# 0_8mm_Layers.net
KiCad netlist of a schematic drawn in EAGLE
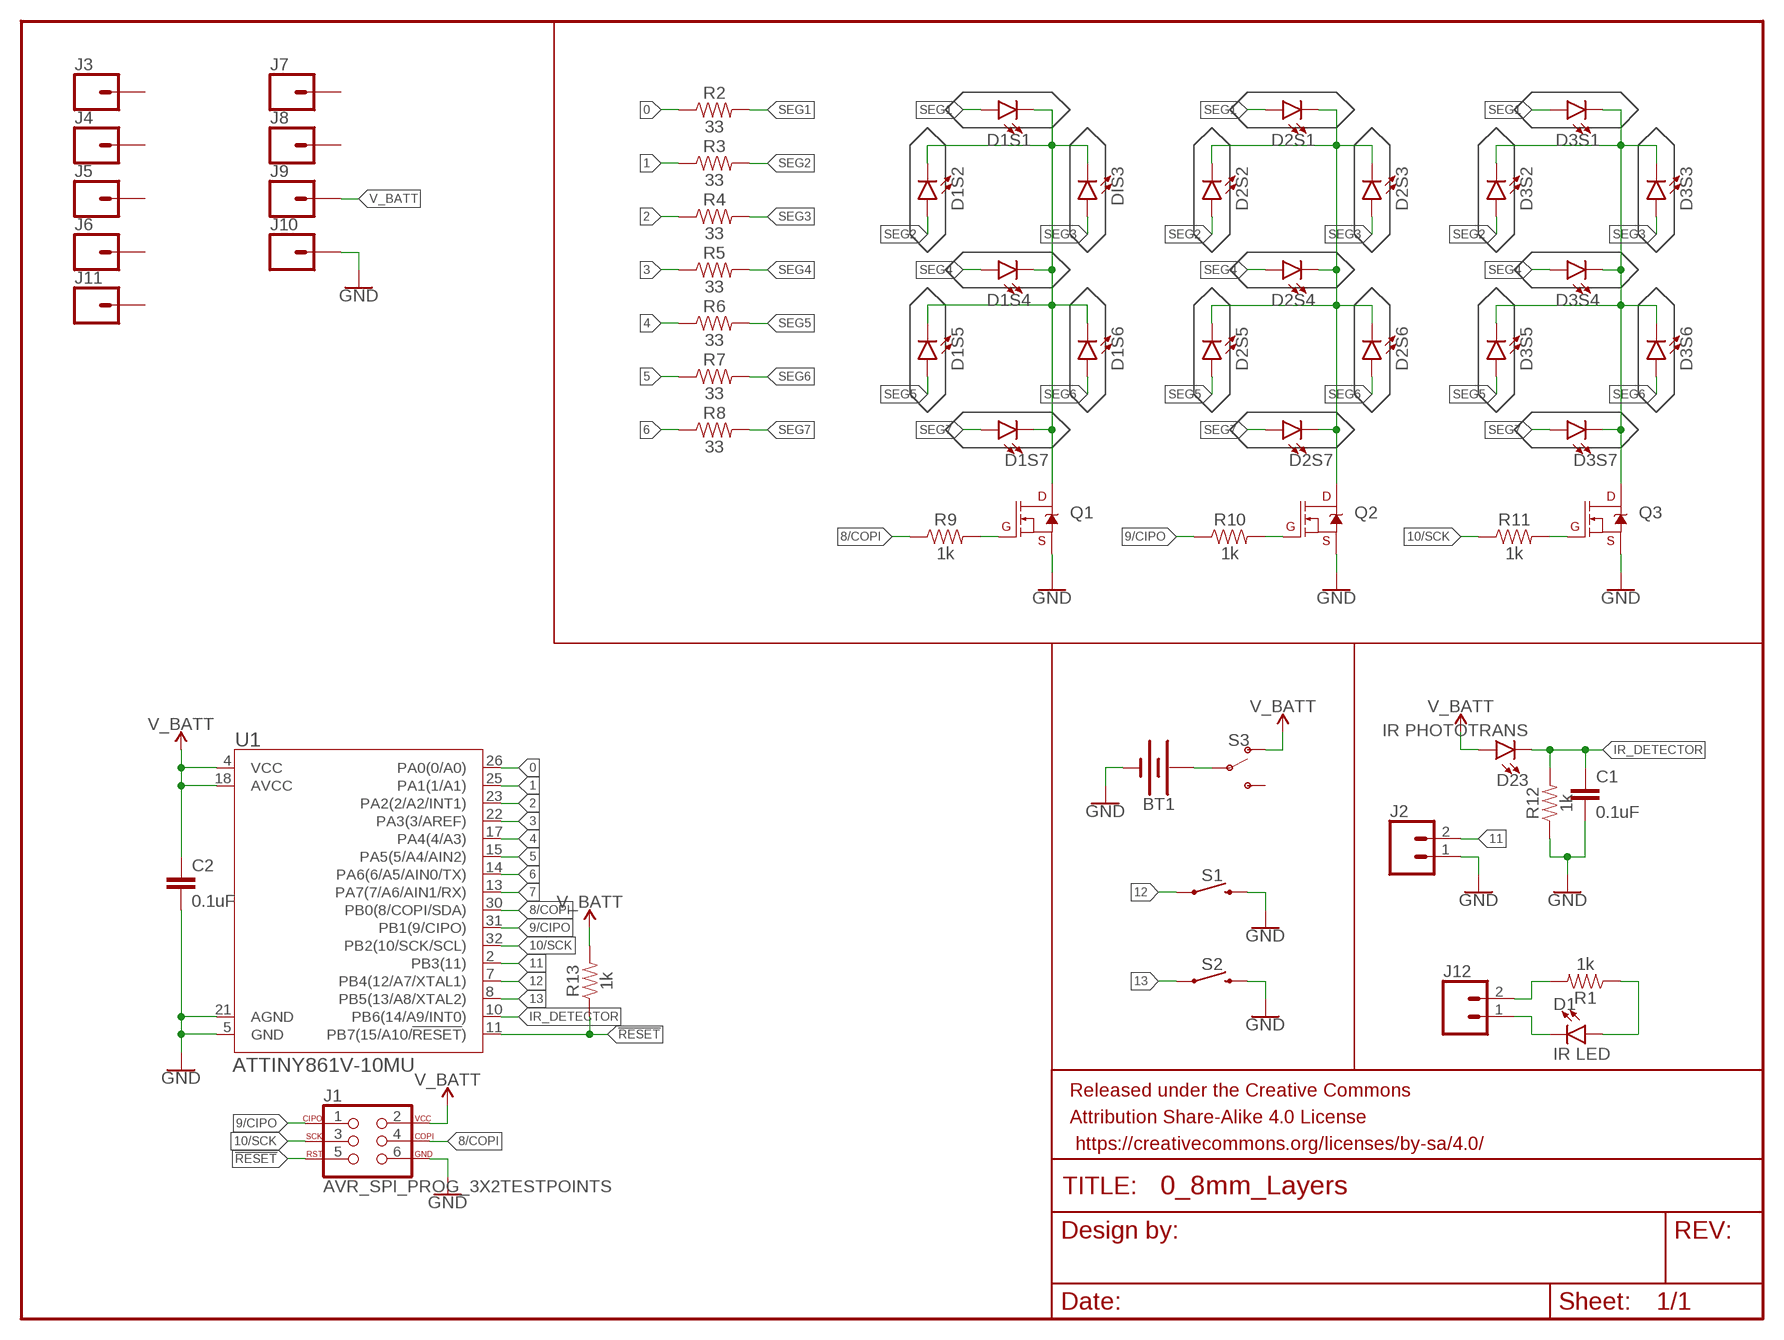
[diagram p0: schematic, sheet 1]

(export (version "E")
  (design (tool "Eeschema 10.0.6"))
  (components
    (comp (ref "BT1")
      (value "BATTERY-20MM_SMD_4LEGS_OVERPASTE_INNER")
      (footprint "eagle-import:BATTCON_20MM_4LEGS_OVERPASTE_INNER")
      (libsource (lib "eagle-import") (part "BATTERY-20MM_SMD_4LEGS_OVERPASTE_INNER"))
    )
    (comp (ref "C1")
      (value "0.1uF")
      (footprint "eagle-import:0603")
      (libsource (lib "eagle-import") (part "0.1UF-0603-25V-(+80/-20%)"))
    )
    (comp (ref "C2")
      (value "0.1uF")
      (footprint "eagle-import:0603")
      (libsource (lib "eagle-import") (part "0.1UF-0603-25V-(+80/-20%)"))
    )
    (comp (ref "D1")
      (value "IR LED")
      (footprint "eagle-import:LED-0603")
      (libsource (lib "eagle-import") (part "LED-IR0603"))
    )
    (comp (ref "D1S1")
      (value "LED0603")
      (footprint "eagle-import:LED-0603")
      (libsource (lib "eagle-import") (part "LED0603"))
    )
    (comp (ref "D1S2")
      (value "LED0603")
      (footprint "eagle-import:LED-0603")
      (libsource (lib "eagle-import") (part "LED0603"))
    )
    (comp (ref "D1S4")
      (value "LED0603")
      (footprint "eagle-import:LED-0603")
      (libsource (lib "eagle-import") (part "LED0603"))
    )
    (comp (ref "D1S5")
      (value "LED0603")
      (footprint "eagle-import:LED-0603")
      (libsource (lib "eagle-import") (part "LED0603"))
    )
    (comp (ref "D1S6")
      (value "LED0603")
      (footprint "eagle-import:LED-0603")
      (libsource (lib "eagle-import") (part "LED0603"))
    )
    (comp (ref "D1S7")
      (value "LED0603")
      (footprint "eagle-import:LED-0603")
      (libsource (lib "eagle-import") (part "LED0603"))
    )
    (comp (ref "D2S1")
      (value "LED0603")
      (footprint "eagle-import:LED-0603")
      (libsource (lib "eagle-import") (part "LED0603"))
    )
    (comp (ref "D2S2")
      (value "LED0603")
      (footprint "eagle-import:LED-0603")
      (libsource (lib "eagle-import") (part "LED0603"))
    )
    (comp (ref "D2S3")
      (value "LED0603")
      (footprint "eagle-import:LED-0603")
      (libsource (lib "eagle-import") (part "LED0603"))
    )
    (comp (ref "D2S4")
      (value "LED0603")
      (footprint "eagle-import:LED-0603")
      (libsource (lib "eagle-import") (part "LED0603"))
    )
    (comp (ref "D2S5")
      (value "LED0603")
      (footprint "eagle-import:LED-0603")
      (libsource (lib "eagle-import") (part "LED0603"))
    )
    (comp (ref "D2S6")
      (value "LED0603")
      (footprint "eagle-import:LED-0603")
      (libsource (lib "eagle-import") (part "LED0603"))
    )
    (comp (ref "D2S7")
      (value "LED0603")
      (footprint "eagle-import:LED-0603")
      (libsource (lib "eagle-import") (part "LED0603"))
    )
    (comp (ref "D3S1")
      (value "LED0603")
      (footprint "eagle-import:LED-0603")
      (libsource (lib "eagle-import") (part "LED0603"))
    )
    (comp (ref "D3S2")
      (value "LED0603")
      (footprint "eagle-import:LED-0603")
      (libsource (lib "eagle-import") (part "LED0603"))
    )
    (comp (ref "D3S3")
      (value "LED0603")
      (footprint "eagle-import:LED-0603")
      (libsource (lib "eagle-import") (part "LED0603"))
    )
    (comp (ref "D3S4")
      (value "LED0603")
      (footprint "eagle-import:LED-0603")
      (libsource (lib "eagle-import") (part "LED0603"))
    )
    (comp (ref "D3S5")
      (value "LED0603")
      (footprint "eagle-import:LED-0603")
      (libsource (lib "eagle-import") (part "LED0603"))
    )
    (comp (ref "D3S6")
      (value "LED0603")
      (footprint "eagle-import:LED-0603")
      (libsource (lib "eagle-import") (part "LED0603"))
    )
    (comp (ref "D3S7")
      (value "LED0603")
      (footprint "eagle-import:LED-0603")
      (libsource (lib "eagle-import") (part "LED0603"))
    )
    (comp (ref "D23")
      (value "IR PHOTOTRANS")
      (footprint "eagle-import:LED-0603")
      (libsource (lib "eagle-import") (part "LED-IR0603"))
    )
    (comp (ref "DIS3")
      (value "LED0603")
      (footprint "eagle-import:LED-0603")
      (libsource (lib "eagle-import") (part "LED0603"))
    )
    (comp (ref "FRAME1")
      (value "FRAME-LETTER")
      (footprint "eagle-import:CREATIVE_COMMONS")
      (libsource (lib "eagle-import") (part "FRAME-LETTER"))
    )
    (comp (ref "J1")
      (value "AVR_SPI_PROG_3X2TESTPOINTS")
      (footprint "eagle-import:2X3_TEST_POINTS")
      (libsource (lib "eagle-import") (part "AVR_SPI_PROG_3X2TESTPOINTS"))
    )
    (comp (ref "J2")
      (value "CONN_02")
      (footprint "eagle-import:1X02")
      (libsource (lib "eagle-import") (part "CONN_02"))
    )
    (comp (ref "J3")
      (value "CONN_01")
      (footprint "eagle-import:1X01")
      (libsource (lib "eagle-import") (part "CONN_01"))
    )
    (comp (ref "J4")
      (value "CONN_01")
      (footprint "eagle-import:1X01")
      (libsource (lib "eagle-import") (part "CONN_01"))
    )
    (comp (ref "J5")
      (value "CONN_01")
      (footprint "eagle-import:1X01")
      (libsource (lib "eagle-import") (part "CONN_01"))
    )
    (comp (ref "J6")
      (value "CONN_01")
      (footprint "eagle-import:1X01")
      (libsource (lib "eagle-import") (part "CONN_01"))
    )
    (comp (ref "J7")
      (value "CONN_01")
      (footprint "eagle-import:1X01")
      (libsource (lib "eagle-import") (part "CONN_01"))
    )
    (comp (ref "J8")
      (value "CONN_01")
      (footprint "eagle-import:1X01")
      (libsource (lib "eagle-import") (part "CONN_01"))
    )
    (comp (ref "J9")
      (value "CONN_01")
      (footprint "eagle-import:1X01")
      (libsource (lib "eagle-import") (part "CONN_01"))
    )
    (comp (ref "J10")
      (value "CONN_01")
      (footprint "eagle-import:1X01")
      (libsource (lib "eagle-import") (part "CONN_01"))
    )
    (comp (ref "J11")
      (value "CONN_01")
      (footprint "eagle-import:1X01")
      (libsource (lib "eagle-import") (part "CONN_01"))
    )
    (comp (ref "J12")
      (value "CONN_02")
      (footprint "eagle-import:1X02")
      (libsource (lib "eagle-import") (part "CONN_02"))
    )
    (comp (ref "Q1")
      (value "220mA/50V/3.5Ω")
      (footprint "eagle-import:SOT23-3")
      (libsource (lib "eagle-import") (part "MOSFET-NCH-BSS138"))
    )
    (comp (ref "Q2")
      (value "220mA/50V/3.5Ω")
      (footprint "eagle-import:SOT23-3")
      (libsource (lib "eagle-import") (part "MOSFET-NCH-BSS138"))
    )
    (comp (ref "Q3")
      (value "220mA/50V/3.5Ω")
      (footprint "eagle-import:SOT23-3")
      (libsource (lib "eagle-import") (part "MOSFET-NCH-BSS138"))
    )
    (comp (ref "R1")
      (value "1k")
      (footprint "eagle-import:0603")
      (libsource (lib "eagle-import") (part "1KOHM-0603-1/10W-1%"))
    )
    (comp (ref "R2")
      (value "33")
      (footprint "eagle-import:0603")
      (libsource (lib "eagle-import") (part "33OHM-0603-1/10W-1%"))
    )
    (comp (ref "R3")
      (value "33")
      (footprint "eagle-import:0603")
      (libsource (lib "eagle-import") (part "33OHM-0603-1/10W-1%"))
    )
    (comp (ref "R4")
      (value "33")
      (footprint "eagle-import:0603")
      (libsource (lib "eagle-import") (part "33OHM-0603-1/10W-1%"))
    )
    (comp (ref "R5")
      (value "33")
      (footprint "eagle-import:0603")
      (libsource (lib "eagle-import") (part "33OHM-0603-1/10W-1%"))
    )
    (comp (ref "R6")
      (value "33")
      (footprint "eagle-import:0603")
      (libsource (lib "eagle-import") (part "33OHM-0603-1/10W-1%"))
    )
    (comp (ref "R7")
      (value "33")
      (footprint "eagle-import:0603")
      (libsource (lib "eagle-import") (part "33OHM-0603-1/10W-1%"))
    )
    (comp (ref "R8")
      (value "33")
      (footprint "eagle-import:0603")
      (libsource (lib "eagle-import") (part "33OHM-0603-1/10W-1%"))
    )
    (comp (ref "R9")
      (value "1k")
      (footprint "eagle-import:0603")
      (libsource (lib "eagle-import") (part "1KOHM-0603-1/10W-1%"))
    )
    (comp (ref "R10")
      (value "1k")
      (footprint "eagle-import:0603")
      (libsource (lib "eagle-import") (part "1KOHM-0603-1/10W-1%"))
    )
    (comp (ref "R11")
      (value "1k")
      (footprint "eagle-import:0603")
      (libsource (lib "eagle-import") (part "1KOHM-0603-1/10W-1%"))
    )
    (comp (ref "R12")
      (value "1k")
      (footprint "eagle-import:0603")
      (libsource (lib "eagle-import") (part "1KOHM-0603-1/10W-1%"))
    )
    (comp (ref "R13")
      (value "1k")
      (footprint "eagle-import:0603")
      (libsource (lib "eagle-import") (part "1KOHM-0603-1/10W-1%"))
    )
    (comp (ref "S1")
      (value "MOMENTARY-SWITCH-SPST-SMD-5.2MM-TALL")
      (footprint "eagle-import:TACTILE_SWITCH_SMD_5.2MM")
      (libsource (lib "eagle-import") (part "MOMENTARY-SWITCH-SPST-SMD-5.2MM-TALL"))
    )
    (comp (ref "S2")
      (value "MOMENTARY-SWITCH-SPST-SMD-5.2MM-TALL")
      (footprint "eagle-import:TACTILE_SWITCH_SMD_5.2MM")
      (libsource (lib "eagle-import") (part "MOMENTARY-SWITCH-SPST-SMD-5.2MM-TALL"))
    )
    (comp (ref "S3")
      (value "SWITCH-SPDT-SMD-RIGHT-ANGLE")
      (footprint "eagle-import:SWITCH_SPST_SMD_A")
      (libsource (lib "eagle-import") (part "SWITCH-SPDT-SMD-RIGHT-ANGLE"))
    )
    (comp (ref "U1")
      (value "ATTINY861V-10MU")
      (footprint "eagle-import:32M1-A_ATM")
      (fields (field (name "COPYRIGHT") "Copyright (C) 2021 Ultra Librarian. All rights reserved."))
      (libsource (lib "eagle-import") (part "ATTINY861V-10MU"))
    )
  )
  (nets
    (net (code "1") (name "/~{RESET}") (class "Default")
      (node (ref "J1") (pin "5") (pinfunction "5_5") (pintype "passive"))
      (node (ref "R13") (pin "1") (pinfunction "1_1") (pintype "passive"))
      (node (ref "U1") (pin "11") (pinfunction "PB7(15/A10/~{RESET})_11") (pintype "bidirectional"))
    )
    (net (code "2") (name "0") (class "Default")
      (node (ref "R2") (pin "1") (pinfunction "1_1") (pintype "passive"))
      (node (ref "U1") (pin "26") (pinfunction "PA0(0/A0)_26") (pintype "bidirectional"))
    )
    (net (code "3") (name "1") (class "Default")
      (node (ref "R3") (pin "1") (pinfunction "1_1") (pintype "passive"))
      (node (ref "U1") (pin "25") (pinfunction "PA1(1/A1)_25") (pintype "bidirectional"))
    )
    (net (code "4") (name "2") (class "Default")
      (node (ref "R4") (pin "1") (pinfunction "1_1") (pintype "passive"))
      (node (ref "U1") (pin "23") (pinfunction "PA2(2/A2/INT1)_23") (pintype "bidirectional"))
    )
    (net (code "5") (name "3") (class "Default")
      (node (ref "R5") (pin "1") (pinfunction "1_1") (pintype "passive"))
      (node (ref "U1") (pin "22") (pinfunction "PA3(3/AREF)_22") (pintype "bidirectional"))
    )
    (net (code "6") (name "4") (class "Default")
      (node (ref "R6") (pin "1") (pinfunction "1_1") (pintype "passive"))
      (node (ref "U1") (pin "17") (pinfunction "PA4(4/A3)_17") (pintype "bidirectional"))
    )
    (net (code "7") (name "5") (class "Default")
      (node (ref "R7") (pin "1") (pinfunction "1_1") (pintype "passive"))
      (node (ref "U1") (pin "15") (pinfunction "PA5(5/A4/AIN2)_15") (pintype "bidirectional"))
    )
    (net (code "8") (name "6") (class "Default")
      (node (ref "R8") (pin "1") (pinfunction "1_1") (pintype "passive"))
      (node (ref "U1") (pin "14") (pinfunction "PA6(6/A5/AIN0/TX)_14") (pintype "bidirectional"))
    )
    (net (code "9") (name "7") (class "Default")
      (node (ref "U1") (pin "13") (pinfunction "PA7(7/A6/AIN1/RX)_13") (pintype "bidirectional"))
    )
    (net (code "10") (name "8{slash}COPI") (class "Default")
      (node (ref "J1") (pin "4") (pinfunction "4_4") (pintype "passive"))
      (node (ref "R9") (pin "1") (pinfunction "1_1") (pintype "passive"))
      (node (ref "U1") (pin "30") (pinfunction "PB0(8/COPI/SDA)_30") (pintype "bidirectional"))
    )
    (net (code "11") (name "9{slash}CIPO") (class "Default")
      (node (ref "J1") (pin "1") (pinfunction "1_1") (pintype "passive"))
      (node (ref "R10") (pin "1") (pinfunction "1_1") (pintype "passive"))
      (node (ref "U1") (pin "31") (pinfunction "PB1(9/CIPO)_31") (pintype "bidirectional"))
    )
    (net (code "12") (name "10{slash}SCK") (class "Default")
      (node (ref "J1") (pin "3") (pinfunction "3_3") (pintype "passive"))
      (node (ref "R11") (pin "1") (pinfunction "1_1") (pintype "passive"))
      (node (ref "U1") (pin "32") (pinfunction "PB2(10/SCK/SCL)_32") (pintype "bidirectional"))
    )
    (net (code "13") (name "11") (class "Default")
      (node (ref "J2") (pin "2") (pinfunction "2_2") (pintype "passive"))
      (node (ref "U1") (pin "2") (pinfunction "PB3(11)_2") (pintype "bidirectional"))
    )
    (net (code "14") (name "12") (class "Default")
      (node (ref "S1") (pin "1") (pinfunction "1_1") (pintype "passive"))
      (node (ref "U1") (pin "7") (pinfunction "PB4(12/A7/XTAL1)_7") (pintype "bidirectional"))
    )
    (net (code "15") (name "13") (class "Default")
      (node (ref "S2") (pin "1") (pinfunction "1_1") (pintype "passive"))
      (node (ref "U1") (pin "8") (pinfunction "PB5(13/A8/XTAL2)_8") (pintype "bidirectional"))
    )
    (net (code "16") (name "GND") (class "Default")
      (node (ref "BT1") (pin "2") (pinfunction "-_2") (pintype "power_in"))
      (node (ref "C1") (pin "2") (pinfunction "2_2") (pintype "passive"))
      (node (ref "C2") (pin "2") (pinfunction "2_2") (pintype "passive"))
      (node (ref "J1") (pin "6") (pinfunction "6_6") (pintype "passive"))
      (node (ref "J10") (pin "1") (pinfunction "1_1") (pintype "passive"))
      (node (ref "J2") (pin "1") (pinfunction "1_1") (pintype "passive"))
      (node (ref "Q1") (pin "2") (pinfunction "S_2") (pintype "bidirectional"))
      (node (ref "Q2") (pin "2") (pinfunction "S_2") (pintype "bidirectional"))
      (node (ref "Q3") (pin "2") (pinfunction "S_2") (pintype "bidirectional"))
      (node (ref "R12") (pin "1") (pinfunction "1_1") (pintype "passive"))
      (node (ref "S1") (pin "3") (pinfunction "2_3") (pintype "passive"))
      (node (ref "S2") (pin "3") (pinfunction "2_3") (pintype "passive"))
      (node (ref "U1") (pin "21") (pinfunction "AGND_21") (pintype "power_in"))
      (node (ref "U1") (pin "5") (pinfunction "GND_5") (pintype "power_in"))
    )
    (net (code "17") (name "IR_DETECTOR") (class "Default")
      (node (ref "C1") (pin "1") (pinfunction "1_1") (pintype "passive"))
      (node (ref "D23") (pin "C") (pinfunction "C_C") (pintype "passive"))
      (node (ref "R12") (pin "2") (pinfunction "2_2") (pintype "passive"))
      (node (ref "U1") (pin "10") (pinfunction "PB6(14/A9/INT0)_10") (pintype "bidirectional"))
    )
    (net (code "18") (name "Net-(BT1-+)") (class "Default")
      (node (ref "BT1") (pin "1") (pinfunction "+_1") (pintype "power_in"))
      (node (ref "S3") (pin "2") (pinfunction "P_2") (pintype "passive"))
    )
    (net (code "19") (name "Net-(D1-PadA)") (class "Default")
      (node (ref "D1") (pin "A") (pinfunction "A_A") (pintype "passive"))
      (node (ref "R1") (pin "1") (pinfunction "1_1") (pintype "passive"))
    )
    (net (code "20") (name "Net-(D1-PadC)") (class "Default")
      (node (ref "D1") (pin "C") (pinfunction "C_C") (pintype "passive"))
      (node (ref "J12") (pin "1") (pinfunction "1_1") (pintype "passive"))
    )
    (net (code "21") (name "Net-(J12-Pad2)") (class "Default")
      (node (ref "J12") (pin "2") (pinfunction "2_2") (pintype "passive"))
      (node (ref "R1") (pin "2") (pinfunction "2_2") (pintype "passive"))
    )
    (net (code "22") (name "Net-(Q1-D)") (class "Default")
      (node (ref "D1S1") (pin "C") (pinfunction "C_C") (pintype "passive"))
      (node (ref "D1S2") (pin "C") (pinfunction "C_C") (pintype "passive"))
      (node (ref "D1S4") (pin "C") (pinfunction "C_C") (pintype "passive"))
      (node (ref "D1S5") (pin "C") (pinfunction "C_C") (pintype "passive"))
      (node (ref "D1S6") (pin "C") (pinfunction "C_C") (pintype "passive"))
      (node (ref "D1S7") (pin "C") (pinfunction "C_C") (pintype "passive"))
      (node (ref "DIS3") (pin "C") (pinfunction "C_C") (pintype "passive"))
      (node (ref "Q1") (pin "3") (pinfunction "D_3") (pintype "bidirectional"))
    )
    (net (code "23") (name "Net-(Q1-G)") (class "Default")
      (node (ref "Q1") (pin "1") (pinfunction "G_1") (pintype "bidirectional"))
      (node (ref "R9") (pin "2") (pinfunction "2_2") (pintype "passive"))
    )
    (net (code "24") (name "Net-(Q2-D)") (class "Default")
      (node (ref "D2S1") (pin "C") (pinfunction "C_C") (pintype "passive"))
      (node (ref "D2S2") (pin "C") (pinfunction "C_C") (pintype "passive"))
      (node (ref "D2S3") (pin "C") (pinfunction "C_C") (pintype "passive"))
      (node (ref "D2S4") (pin "C") (pinfunction "C_C") (pintype "passive"))
      (node (ref "D2S5") (pin "C") (pinfunction "C_C") (pintype "passive"))
      (node (ref "D2S6") (pin "C") (pinfunction "C_C") (pintype "passive"))
      (node (ref "D2S7") (pin "C") (pinfunction "C_C") (pintype "passive"))
      (node (ref "Q2") (pin "3") (pinfunction "D_3") (pintype "bidirectional"))
    )
    (net (code "25") (name "Net-(Q2-G)") (class "Default")
      (node (ref "Q2") (pin "1") (pinfunction "G_1") (pintype "bidirectional"))
      (node (ref "R10") (pin "2") (pinfunction "2_2") (pintype "passive"))
    )
    (net (code "26") (name "Net-(Q3-D)") (class "Default")
      (node (ref "D3S1") (pin "C") (pinfunction "C_C") (pintype "passive"))
      (node (ref "D3S2") (pin "C") (pinfunction "C_C") (pintype "passive"))
      (node (ref "D3S3") (pin "C") (pinfunction "C_C") (pintype "passive"))
      (node (ref "D3S4") (pin "C") (pinfunction "C_C") (pintype "passive"))
      (node (ref "D3S5") (pin "C") (pinfunction "C_C") (pintype "passive"))
      (node (ref "D3S6") (pin "C") (pinfunction "C_C") (pintype "passive"))
      (node (ref "D3S7") (pin "C") (pinfunction "C_C") (pintype "passive"))
      (node (ref "Q3") (pin "3") (pinfunction "D_3") (pintype "bidirectional"))
    )
    (net (code "27") (name "Net-(Q3-G)") (class "Default")
      (node (ref "Q3") (pin "1") (pinfunction "G_1") (pintype "bidirectional"))
      (node (ref "R11") (pin "2") (pinfunction "2_2") (pintype "passive"))
    )
    (net (code "28") (name "SEG1") (class "Default")
      (node (ref "D1S1") (pin "A") (pinfunction "A_A") (pintype "passive"))
      (node (ref "D2S1") (pin "A") (pinfunction "A_A") (pintype "passive"))
      (node (ref "D3S1") (pin "A") (pinfunction "A_A") (pintype "passive"))
      (node (ref "R2") (pin "2") (pinfunction "2_2") (pintype "passive"))
    )
    (net (code "29") (name "SEG2") (class "Default")
      (node (ref "D1S2") (pin "A") (pinfunction "A_A") (pintype "passive"))
      (node (ref "D2S2") (pin "A") (pinfunction "A_A") (pintype "passive"))
      (node (ref "D3S2") (pin "A") (pinfunction "A_A") (pintype "passive"))
      (node (ref "R3") (pin "2") (pinfunction "2_2") (pintype "passive"))
    )
    (net (code "30") (name "SEG3") (class "Default")
      (node (ref "D2S3") (pin "A") (pinfunction "A_A") (pintype "passive"))
      (node (ref "D3S3") (pin "A") (pinfunction "A_A") (pintype "passive"))
      (node (ref "DIS3") (pin "A") (pinfunction "A_A") (pintype "passive"))
      (node (ref "R4") (pin "2") (pinfunction "2_2") (pintype "passive"))
    )
    (net (code "31") (name "SEG4") (class "Default")
      (node (ref "D1S4") (pin "A") (pinfunction "A_A") (pintype "passive"))
      (node (ref "D2S4") (pin "A") (pinfunction "A_A") (pintype "passive"))
      (node (ref "D3S4") (pin "A") (pinfunction "A_A") (pintype "passive"))
      (node (ref "R5") (pin "2") (pinfunction "2_2") (pintype "passive"))
    )
    (net (code "32") (name "SEG5") (class "Default")
      (node (ref "D1S5") (pin "A") (pinfunction "A_A") (pintype "passive"))
      (node (ref "D2S5") (pin "A") (pinfunction "A_A") (pintype "passive"))
      (node (ref "D3S5") (pin "A") (pinfunction "A_A") (pintype "passive"))
      (node (ref "R6") (pin "2") (pinfunction "2_2") (pintype "passive"))
    )
    (net (code "33") (name "SEG6") (class "Default")
      (node (ref "D1S6") (pin "A") (pinfunction "A_A") (pintype "passive"))
      (node (ref "D2S6") (pin "A") (pinfunction "A_A") (pintype "passive"))
      (node (ref "D3S6") (pin "A") (pinfunction "A_A") (pintype "passive"))
      (node (ref "R7") (pin "2") (pinfunction "2_2") (pintype "passive"))
    )
    (net (code "34") (name "SEG7") (class "Default")
      (node (ref "D1S7") (pin "A") (pinfunction "A_A") (pintype "passive"))
      (node (ref "D2S7") (pin "A") (pinfunction "A_A") (pintype "passive"))
      (node (ref "D3S7") (pin "A") (pinfunction "A_A") (pintype "passive"))
      (node (ref "R8") (pin "2") (pinfunction "2_2") (pintype "passive"))
    )
    (net (code "35") (name "V_BATT") (class "Default")
      (node (ref "C2") (pin "1") (pinfunction "1_1") (pintype "passive"))
      (node (ref "D23") (pin "A") (pinfunction "A_A") (pintype "passive"))
      (node (ref "J1") (pin "2") (pinfunction "2_2") (pintype "passive"))
      (node (ref "J9") (pin "1") (pinfunction "1_1") (pintype "passive"))
      (node (ref "R13") (pin "2") (pinfunction "2_2") (pintype "passive"))
      (node (ref "S3") (pin "1") (pinfunction "O_1") (pintype "passive"))
      (node (ref "U1") (pin "18") (pinfunction "AVCC_18") (pintype "power_in"))
      (node (ref "U1") (pin "4") (pinfunction "VCC_4") (pintype "power_in"))
    )
    (net (code "36") (name "unconnected-(J3-Pad1)") (class "Default")
      (node (ref "J3") (pin "1") (pinfunction "1_1") (pintype "passive"))
    )
    (net (code "37") (name "unconnected-(J4-Pad1)") (class "Default")
      (node (ref "J4") (pin "1") (pinfunction "1_1") (pintype "passive"))
    )
    (net (code "38") (name "unconnected-(J5-Pad1)") (class "Default")
      (node (ref "J5") (pin "1") (pinfunction "1_1") (pintype "passive"))
    )
    (net (code "39") (name "unconnected-(J6-Pad1)") (class "Default")
      (node (ref "J6") (pin "1") (pinfunction "1_1") (pintype "passive"))
    )
    (net (code "40") (name "unconnected-(J7-Pad1)") (class "Default")
      (node (ref "J7") (pin "1") (pinfunction "1_1") (pintype "passive"))
    )
    (net (code "41") (name "unconnected-(J8-Pad1)") (class "Default")
      (node (ref "J8") (pin "1") (pinfunction "1_1") (pintype "passive"))
    )
    (net (code "42") (name "unconnected-(J11-Pad1)") (class "Default")
      (node (ref "J11") (pin "1") (pinfunction "1_1") (pintype "passive"))
    )
    (net (code "43") (name "unconnected-(S3-S-Pad3)") (class "Default")
      (node (ref "S3") (pin "3") (pinfunction "S_3") (pintype "passive"))
    )
  )
)
